# RH016_1.net
KiCad netlist of a schematic drawn in EAGLE
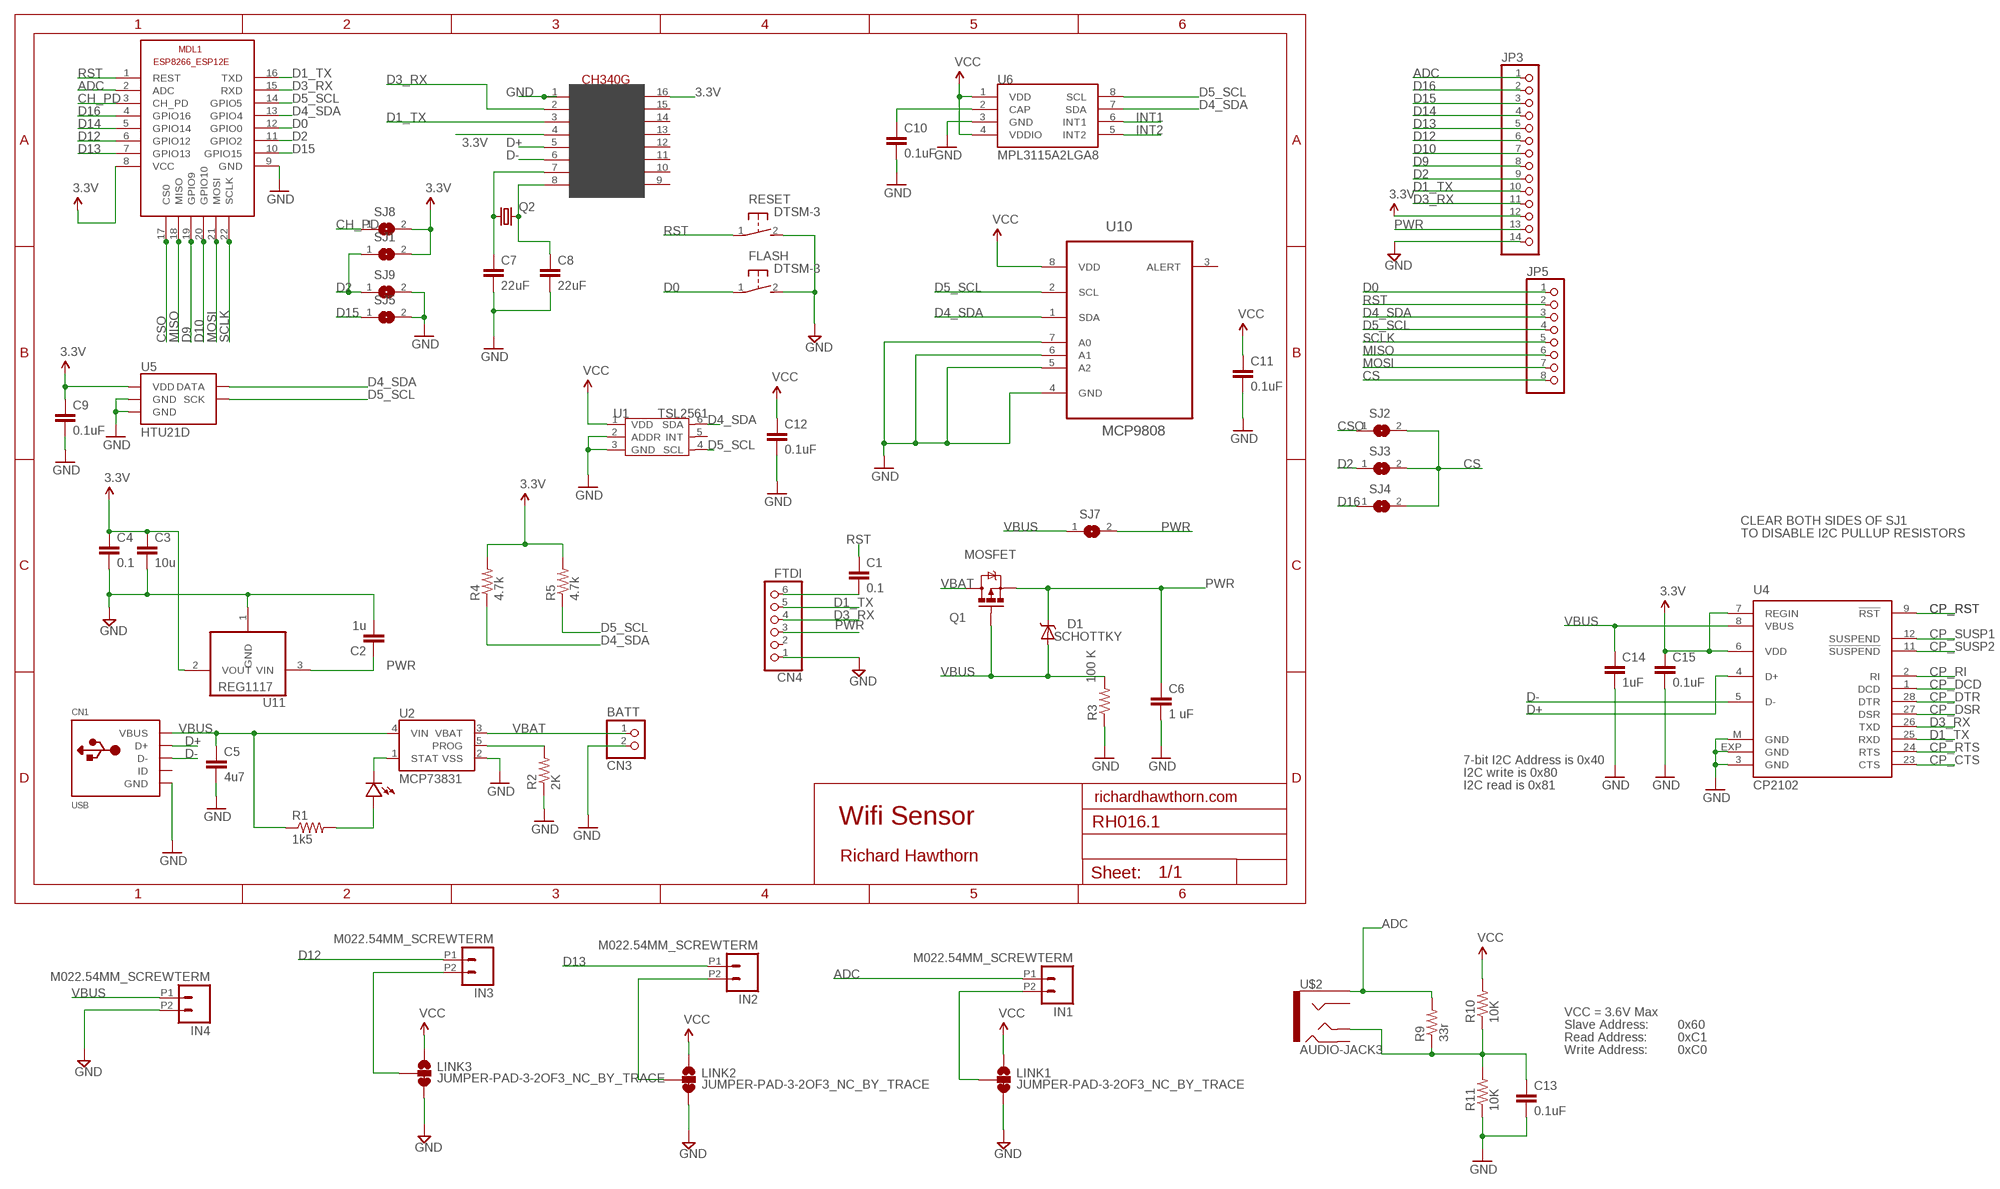
[diagram p0: schematic, sheet 1]

(export (version "E")
  (design (tool "Eeschema 10.0.6"))
  (components
    (comp (ref "C1")
      (value "0.1")
      (footprint "eagle-import:0603-CAP")
      (libsource (lib "eagle-import") (part "CAP0603-CAP"))
    )
    (comp (ref "C2")
      (value "1u")
      (footprint "eagle-import:0603-CAP")
      (libsource (lib "eagle-import") (part "CAP0603-CAP"))
    )
    (comp (ref "C3")
      (value "10u")
      (footprint "eagle-import:0805-CAP")
      (libsource (lib "eagle-import") (part "CAP0805-CAP"))
    )
    (comp (ref "C4")
      (value "0.1")
      (footprint "eagle-import:0603-CAP")
      (libsource (lib "eagle-import") (part "CAP0603-CAP"))
    )
    (comp (ref "C5")
      (value "4u7")
      (footprint "eagle-import:0603-CAP")
      (libsource (lib "eagle-import") (part "SparkFun_CAP0603-CAP"))
    )
    (comp (ref "C6")
      (value "1 uF")
      (footprint "eagle-import:0805")
      (libsource (lib "eagle-import") (part "SparkFun-Capacitors_CAP0805"))
    )
    (comp (ref "C7")
      (value "22uF")
      (footprint "eagle-import:0805")
      (libsource (lib "eagle-import") (part "SparkFun_CAP0805"))
    )
    (comp (ref "C8")
      (value "22uF")
      (footprint "eagle-import:0805")
      (libsource (lib "eagle-import") (part "SparkFun_CAP0805"))
    )
    (comp (ref "C9")
      (value "0.1uF")
      (footprint "eagle-import:0805")
      (libsource (lib "eagle-import") (part "SparkFun_CAP0805"))
    )
    (comp (ref "C10")
      (value "0.1uF")
      (footprint "eagle-import:0805")
      (libsource (lib "eagle-import") (part "SparkFun_CAP0805"))
    )
    (comp (ref "C11")
      (value "0.1uF")
      (footprint "eagle-import:0603-CAP")
      (libsource (lib "eagle-import") (part "SparkFun_CAP0603-CAP"))
    )
    (comp (ref "C12")
      (value "0.1uF")
      (footprint "eagle-import:0603-CAP")
      (libsource (lib "eagle-import") (part "SparkFun_CAP0603-CAP"))
    )
    (comp (ref "C13")
      (value "0.1uF")
      (footprint "eagle-import:0603-CAP")
      (libsource (lib "eagle-import") (part "SparkFun_CAP0603-CAP"))
    )
    (comp (ref "C14")
      (value "1uF")
      (footprint "eagle-import:0603-CAP")
      (libsource (lib "eagle-import") (part "SparkFun_CAP0603-CAP"))
    )
    (comp (ref "C15")
      (value "0.1uF")
      (footprint "eagle-import:0603-CAP")
      (libsource (lib "eagle-import") (part "SparkFun_CAP0603-CAP"))
    )
    (comp (ref "CN1")
      (value "USB")
      (footprint "eagle-import:USB-MINIB")
      (libsource (lib "eagle-import") (part "USBMINIB"))
    )
    (comp (ref "CN3")
      (value "BATT")
      (footprint "eagle-import:JST-PH-2-SMT-RA")
      (libsource (lib "eagle-import") (part "JST_2PIN-SMT-RA"))
    )
    (comp (ref "CN4")
      (value "FTDI")
      (footprint "eagle-import:1X06")
      (libsource (lib "eagle-import") (part "PINHD-1X6"))
    )
    (comp (ref "D1")
      (value "SCHOTTKY")
      (footprint "eagle-import:SMA-DIODE")
      (libsource (lib "eagle-import") (part "DIODE-SCHOTTKY_"))
    )
    (comp (ref "FLASH")
      (value "DTSM-3")
      (footprint "eagle-import:DTSM-3")
      (libsource (lib "eagle-import") (part "DTSM-3"))
    )
    (comp (ref "IN1")
      (value "M022.54MM_SCREWTERM")
      (footprint "eagle-import:1X02_2.54_SCREWTERM")
      (libsource (lib "eagle-import") (part "M022.54MM_SCREWTERM"))
    )
    (comp (ref "IN2")
      (value "M022.54MM_SCREWTERM")
      (footprint "eagle-import:1X02_2.54_SCREWTERM")
      (libsource (lib "eagle-import") (part "M022.54MM_SCREWTERM"))
    )
    (comp (ref "IN3")
      (value "M022.54MM_SCREWTERM")
      (footprint "eagle-import:1X02_2.54_SCREWTERM")
      (libsource (lib "eagle-import") (part "M022.54MM_SCREWTERM"))
    )
    (comp (ref "IN4")
      (value "M022.54MM_SCREWTERM")
      (footprint "eagle-import:1X02_2.54_SCREWTERM")
      (libsource (lib "eagle-import") (part "M022.54MM_SCREWTERM"))
    )
    (comp (ref "JP3")
      (value "PINHD-1X14")
      (footprint "eagle-import:1X14")
      (libsource (lib "eagle-import") (part "PINHD-1X14"))
    )
    (comp (ref "JP5")
      (value "PINHD-1X8")
      (footprint "eagle-import:1X08")
      (libsource (lib "eagle-import") (part "PINHD-1X8"))
    )
    (comp (ref "LED1")
      (value "LED0603")
      (footprint "eagle-import:0603-LED")
      (libsource (lib "eagle-import") (part "LED0603"))
    )
    (comp (ref "LINK1")
      (value "JUMPER-PAD-3-2OF3_NC_BY_TRACE")
      (footprint "eagle-import:PAD-JUMPER-3-2OF3_NC_BY_TRACE_YES_SILK_FULL_BOX")
      (libsource (lib "eagle-import") (part "JUMPER-PAD-3-2OF3_NC_BY_TRACE"))
    )
    (comp (ref "LINK2")
      (value "JUMPER-PAD-3-2OF3_NC_BY_TRACE")
      (footprint "eagle-import:PAD-JUMPER-3-2OF3_NC_BY_TRACE_YES_SILK_FULL_BOX")
      (libsource (lib "eagle-import") (part "JUMPER-PAD-3-2OF3_NC_BY_TRACE"))
    )
    (comp (ref "LINK3")
      (value "JUMPER-PAD-3-2OF3_NC_BY_TRACE")
      (footprint "eagle-import:PAD-JUMPER-3-2OF3_NC_BY_TRACE_YES_SILK_FULL_BOX")
      (libsource (lib "eagle-import") (part "JUMPER-PAD-3-2OF3_NC_BY_TRACE"))
    )
    (comp (ref "MDL1")
      (value "ESP8266-12EESP8266-ESP12E")
      (footprint "eagle-import:ESP8266-ESP12E")
      (libsource (lib "eagle-import") (part "ESP8266-12EESP8266-ESP12E"))
    )
    (comp (ref "Q1")
      (value "MOSFET")
      (footprint "eagle-import:SOT23-3")
      (libsource (lib "eagle-import") (part "MOSFET-PCHANNELSMD"))
    )
    (comp (ref "Q2")
      (value "CRYSTALSM49")
      (footprint "eagle-import:SM49")
      (libsource (lib "eagle-import") (part "CRYSTALSM49"))
    )
    (comp (ref "R1")
      (value "1k5")
      (footprint "eagle-import:0603-RES")
      (libsource (lib "eagle-import") (part "RESISTOR0603-RES"))
    )
    (comp (ref "R2")
      (value "2K")
      (footprint "eagle-import:0603-RES")
      (libsource (lib "eagle-import") (part "RESISTOR0603-RES"))
    )
    (comp (ref "R3")
      (value "100 K")
      (footprint "eagle-import:0805")
      (libsource (lib "eagle-import") (part "SparkFun-Resistors_RESISTOR0805-RES"))
    )
    (comp (ref "R4")
      (value "4.7k")
      (footprint "eagle-import:0805")
      (libsource (lib "eagle-import") (part "SparkFun_RESISTOR0805-RES"))
    )
    (comp (ref "R5")
      (value "4.7k")
      (footprint "eagle-import:0805")
      (libsource (lib "eagle-import") (part "SparkFun_RESISTOR0805-RES"))
    )
    (comp (ref "R9")
      (value "33r")
      (footprint "eagle-import:0603-RES")
      (libsource (lib "eagle-import") (part "SparkFun_RESISTOR0603-RES"))
    )
    (comp (ref "R10")
      (value "10K")
      (footprint "eagle-import:0603-RES")
      (libsource (lib "eagle-import") (part "SparkFun_RESISTOR0603-RES"))
    )
    (comp (ref "R11")
      (value "10K")
      (footprint "eagle-import:0603-RES")
      (libsource (lib "eagle-import") (part "SparkFun_RESISTOR0603-RES"))
    )
    (comp (ref "RESET")
      (value "DTSM-3")
      (footprint "eagle-import:DTSM-3")
      (libsource (lib "eagle-import") (part "DTSM-3"))
    )
    (comp (ref "SJ1") (value "SJ") (footprint "eagle-import:SJ") (libsource (lib "eagle-import") (part "SJ")))
    (comp (ref "SJ2") (value "SJ") (footprint "eagle-import:SJ") (libsource (lib "eagle-import") (part "SJ")))
    (comp (ref "SJ3") (value "SJ") (footprint "eagle-import:SJ") (libsource (lib "eagle-import") (part "SJ")))
    (comp (ref "SJ4") (value "SJ") (footprint "eagle-import:SJ") (libsource (lib "eagle-import") (part "SJ")))
    (comp (ref "SJ5") (value "SJ") (footprint "eagle-import:SJ") (libsource (lib "eagle-import") (part "SJ")))
    (comp (ref "SJ7") (value "SJ") (footprint "eagle-import:SJ") (libsource (lib "eagle-import") (part "SJ")))
    (comp (ref "SJ8") (value "SJ") (footprint "eagle-import:SJ") (libsource (lib "eagle-import") (part "SJ")))
    (comp (ref "SJ9") (value "SJ") (footprint "eagle-import:SJ") (libsource (lib "eagle-import") (part "SJ")))
    (comp (ref "U$2")
      (value "AUDIO-JACK3")
      (footprint "eagle-import:AUDIO-JACK-TRRS-SMD")
      (libsource (lib "eagle-import") (part "AUDIO-JACK3"))
    )
    (comp (ref "U$4")
      (value "CH340G")
      (footprint "eagle-import:SOIC16")
      (libsource (lib "eagle-import") (part "CH340G"))
    )
    (comp (ref "U1")
      (value "TSL2561")
      (footprint "eagle-import:TMB-6")
      (libsource (lib "eagle-import") (part "TSL2561T"))
    )
    (comp (ref "U2")
      (value "MCP73831")
      (footprint "eagle-import:SOT23-5")
      (libsource (lib "eagle-import") (part "MCP73831"))
    )
    (comp (ref "U4")
      (value "CP2102")
      (footprint "eagle-import:MLP28")
      (libsource (lib "eagle-import") (part "CP210X_USB_UART"))
    )
    (comp (ref "U5")
      (value "HTU21D")
      (footprint "eagle-import:HTU21D")
      (libsource (lib "eagle-import") (part "HTU21DSMD"))
    )
    (comp (ref "U6")
      (value "MPL3115A2LGA8")
      (footprint "eagle-import:LGA8")
      (libsource (lib "eagle-import") (part "MPL3115A2LGA8"))
    )
    (comp (ref "U10")
      (value "MCP9808")
      (footprint "eagle-import:SOP65P490X110-8N")
      (fields (field (name "MPN") "MCP9808-E/MS"))
      (libsource (lib "eagle-import") (part "MCP9808-E/MS"))
    )
    (comp (ref "U11")
      (value "REG1117")
      (footprint "eagle-import:SOT223")
      (libsource (lib "eagle-import") (part "REG1117"))
    )
  )
  (nets
    (net (code "1") (name "/ADC") (class "Default")
      (node (ref "IN1") (pin "P1") (pinfunction "1_P1") (pintype "passive"))
      (node (ref "JP3") (pin "1") (pinfunction "1_1") (pintype "passive"))
      (node (ref "MDL1") (pin "2") (pinfunction "ADC_2") (pintype "bidirectional"))
      (node (ref "R9") (pin "2") (pinfunction "2_2") (pintype "passive"))
      (node (ref "U$2") (pin "EARTH") (pinfunction "EARTH_EARTH") (pintype "bidirectional"))
    )
    (net (code "2") (name "/CH_PD") (class "Default")
      (node (ref "MDL1") (pin "3") (pinfunction "CH_PD_3") (pintype "bidirectional"))
      (node (ref "SJ8") (pin "1") (pinfunction "1_1") (pintype "passive"))
    )
    (net (code "3") (name "/CP_CTS") (class "Default")
      (node (ref "U4") (pin "23") (pinfunction "CTS_23") (pintype "input"))
    )
    (net (code "4") (name "/CP_DCD") (class "Default")
      (node (ref "U4") (pin "1") (pinfunction "DCD_1") (pintype "input"))
    )
    (net (code "5") (name "/CP_DSR") (class "Default")
      (node (ref "U4") (pin "27") (pinfunction "DSR_27") (pintype "input"))
    )
    (net (code "6") (name "/CP_DTR") (class "Default")
      (node (ref "U4") (pin "28") (pinfunction "DTR_28") (pintype "output"))
    )
    (net (code "7") (name "/CP_RI") (class "Default")
      (node (ref "U4") (pin "2") (pinfunction "RI_2") (pintype "input"))
    )
    (net (code "8") (name "/CP_RST") (class "Default")
      (node (ref "U4") (pin "9") (pinfunction "~{RST}_9") (pintype "bidirectional"))
    )
    (net (code "9") (name "/CP_RTS") (class "Default")
      (node (ref "U4") (pin "24") (pinfunction "RTS_24") (pintype "output"))
    )
    (net (code "10") (name "/CP_SUSP1") (class "Default")
      (node (ref "U4") (pin "12") (pinfunction "SUSPEND_12") (pintype "output"))
    )
    (net (code "11") (name "/CP_SUSP2") (class "Default")
      (node (ref "U4") (pin "11") (pinfunction "~{SUSPEND}_11") (pintype "output"))
    )
    (net (code "12") (name "/CS") (class "Default")
      (node (ref "JP5") (pin "8") (pinfunction "8_8") (pintype "passive"))
      (node (ref "SJ2") (pin "2") (pinfunction "2_2") (pintype "passive"))
      (node (ref "SJ3") (pin "2") (pinfunction "2_2") (pintype "passive"))
      (node (ref "SJ4") (pin "2") (pinfunction "2_2") (pintype "passive"))
    )
    (net (code "13") (name "/CSO") (class "Default")
      (node (ref "MDL1") (pin "17") (pinfunction "CS0_17") (pintype "bidirectional"))
      (node (ref "SJ2") (pin "1") (pinfunction "1_1") (pintype "passive"))
    )
    (net (code "14") (name "/D+") (class "Default")
      (node (ref "CN1") (pin "D+") (pinfunction "D+_D+") (pintype "bidirectional"))
      (node (ref "U$4") (pin "5") (pinfunction "D+_5") (pintype "bidirectional"))
      (node (ref "U4") (pin "4") (pinfunction "D+_4") (pintype "bidirectional"))
    )
    (net (code "15") (name "/D-") (class "Default")
      (node (ref "CN1") (pin "D-") (pinfunction "D-_D-") (pintype "bidirectional"))
      (node (ref "U$4") (pin "6") (pinfunction "D-_6") (pintype "bidirectional"))
      (node (ref "U4") (pin "5") (pinfunction "D-_5") (pintype "bidirectional"))
    )
    (net (code "16") (name "/D0") (class "Default")
      (node (ref "FLASH") (pin "1") (pinfunction "1_1") (pintype "passive"))
      (node (ref "JP5") (pin "1") (pinfunction "1_1") (pintype "passive"))
      (node (ref "MDL1") (pin "12") (pinfunction "GPIO0_12") (pintype "bidirectional"))
    )
    (net (code "17") (name "/D1_TX") (class "Default")
      (node (ref "CN4") (pin "5") (pinfunction "5_5") (pintype "passive"))
      (node (ref "JP3") (pin "10") (pinfunction "10_10") (pintype "passive"))
      (node (ref "MDL1") (pin "16") (pinfunction "TXD_16") (pintype "bidirectional"))
      (node (ref "U$4") (pin "3") (pinfunction "RX_3") (pintype "bidirectional"))
      (node (ref "U4") (pin "25") (pinfunction "RXD_25") (pintype "input"))
    )
    (net (code "18") (name "/D2") (class "Default")
      (node (ref "JP3") (pin "9") (pinfunction "9_9") (pintype "passive"))
      (node (ref "MDL1") (pin "11") (pinfunction "GPIO2_11") (pintype "bidirectional"))
      (node (ref "SJ1") (pin "1") (pinfunction "1_1") (pintype "passive"))
      (node (ref "SJ3") (pin "1") (pinfunction "1_1") (pintype "passive"))
      (node (ref "SJ9") (pin "1") (pinfunction "1_1") (pintype "passive"))
    )
    (net (code "19") (name "/D3_RX") (class "Default")
      (node (ref "CN4") (pin "4") (pinfunction "4_4") (pintype "passive"))
      (node (ref "JP3") (pin "11") (pinfunction "11_11") (pintype "passive"))
      (node (ref "MDL1") (pin "15") (pinfunction "RXD_15") (pintype "bidirectional"))
      (node (ref "U$4") (pin "2") (pinfunction "TX_2") (pintype "bidirectional"))
      (node (ref "U4") (pin "26") (pinfunction "TXD_26") (pintype "output"))
    )
    (net (code "20") (name "/D4_SDA") (class "Default")
      (node (ref "JP5") (pin "3") (pinfunction "3_3") (pintype "passive"))
      (node (ref "MDL1") (pin "13") (pinfunction "GPIO4_13") (pintype "bidirectional"))
      (node (ref "R4") (pin "1") (pinfunction "1_1") (pintype "passive"))
      (node (ref "U1") (pin "6") (pinfunction "SDA_6") (pintype "bidirectional"))
      (node (ref "U10") (pin "1") (pinfunction "SDA_1") (pintype "bidirectional"))
      (node (ref "U5") (pin "DATA") (pinfunction "DATA_DATA") (pintype "bidirectional"))
      (node (ref "U6") (pin "7") (pinfunction "SDA_7") (pintype "bidirectional"))
    )
    (net (code "21") (name "/D5_SCL") (class "Default")
      (node (ref "JP5") (pin "4") (pinfunction "4_4") (pintype "passive"))
      (node (ref "MDL1") (pin "14") (pinfunction "GPIO5_14") (pintype "bidirectional"))
      (node (ref "R5") (pin "1") (pinfunction "1_1") (pintype "passive"))
      (node (ref "U1") (pin "4") (pinfunction "SCL_4") (pintype "input"))
      (node (ref "U10") (pin "2") (pinfunction "SCL_2") (pintype "input"))
      (node (ref "U5") (pin "SCK") (pinfunction "SCK_SCK") (pintype "input"))
      (node (ref "U6") (pin "8") (pinfunction "SCL_8") (pintype "bidirectional"))
    )
    (net (code "22") (name "/D9") (class "Default")
      (node (ref "JP3") (pin "8") (pinfunction "8_8") (pintype "passive"))
      (node (ref "MDL1") (pin "19") (pinfunction "GPIO9_19") (pintype "bidirectional"))
    )
    (net (code "23") (name "/D10") (class "Default")
      (node (ref "JP3") (pin "7") (pinfunction "7_7") (pintype "passive"))
      (node (ref "MDL1") (pin "20") (pinfunction "GPIO10_20") (pintype "bidirectional"))
    )
    (net (code "24") (name "/D12") (class "Default")
      (node (ref "IN3") (pin "P1") (pinfunction "1_P1") (pintype "passive"))
      (node (ref "JP3") (pin "6") (pinfunction "6_6") (pintype "passive"))
      (node (ref "MDL1") (pin "6") (pinfunction "GPIO12_6") (pintype "bidirectional"))
    )
    (net (code "25") (name "/D13") (class "Default")
      (node (ref "IN2") (pin "P1") (pinfunction "1_P1") (pintype "passive"))
      (node (ref "JP3") (pin "5") (pinfunction "5_5") (pintype "passive"))
      (node (ref "MDL1") (pin "7") (pinfunction "GPIO13_7") (pintype "bidirectional"))
    )
    (net (code "26") (name "/D14") (class "Default")
      (node (ref "JP3") (pin "4") (pinfunction "4_4") (pintype "passive"))
      (node (ref "MDL1") (pin "5") (pinfunction "GPIO14_5") (pintype "bidirectional"))
    )
    (net (code "27") (name "/D15") (class "Default")
      (node (ref "JP3") (pin "3") (pinfunction "3_3") (pintype "passive"))
      (node (ref "MDL1") (pin "10") (pinfunction "GPIO15_10") (pintype "bidirectional"))
      (node (ref "SJ5") (pin "1") (pinfunction "1_1") (pintype "passive"))
    )
    (net (code "28") (name "/D16") (class "Default")
      (node (ref "JP3") (pin "2") (pinfunction "2_2") (pintype "passive"))
      (node (ref "MDL1") (pin "4") (pinfunction "GPIO16_4") (pintype "bidirectional"))
      (node (ref "SJ4") (pin "1") (pinfunction "1_1") (pintype "passive"))
    )
    (net (code "29") (name "/INT1") (class "Default")
      (node (ref "U6") (pin "6") (pinfunction "INT1_6") (pintype "bidirectional"))
    )
    (net (code "30") (name "/INT2") (class "Default")
      (node (ref "U6") (pin "5") (pinfunction "INT2_5") (pintype "bidirectional"))
    )
    (net (code "31") (name "/MISO") (class "Default")
      (node (ref "JP5") (pin "6") (pinfunction "6_6") (pintype "passive"))
      (node (ref "MDL1") (pin "18") (pinfunction "MISO_18") (pintype "bidirectional"))
    )
    (net (code "32") (name "/MOSI") (class "Default")
      (node (ref "JP5") (pin "7") (pinfunction "7_7") (pintype "passive"))
      (node (ref "MDL1") (pin "21") (pinfunction "MOSI_21") (pintype "bidirectional"))
    )
    (net (code "33") (name "/PWR") (class "Default")
      (node (ref "C2") (pin "1") (pinfunction "1_1") (pintype "passive"))
      (node (ref "C6") (pin "1") (pinfunction "1_1") (pintype "passive"))
      (node (ref "CN4") (pin "3") (pinfunction "3_3") (pintype "passive"))
      (node (ref "D1") (pin "C") (pinfunction "C_C") (pintype "passive"))
      (node (ref "JP3") (pin "13") (pinfunction "13_13") (pintype "passive"))
      (node (ref "Q1") (pin "2") (pinfunction "S_2") (pintype "passive"))
      (node (ref "SJ7") (pin "2") (pinfunction "2_2") (pintype "passive"))
      (node (ref "U11") (pin "3") (pinfunction "VIN_3") (pintype "input"))
    )
    (net (code "34") (name "/RST") (class "Default")
      (node (ref "C1") (pin "1") (pinfunction "1_1") (pintype "passive"))
      (node (ref "JP5") (pin "2") (pinfunction "2_2") (pintype "passive"))
      (node (ref "MDL1") (pin "1") (pinfunction "REST_1") (pintype "bidirectional"))
      (node (ref "RESET") (pin "1") (pinfunction "1_1") (pintype "passive"))
    )
    (net (code "35") (name "/SCLK") (class "Default")
      (node (ref "JP5") (pin "5") (pinfunction "5_5") (pintype "passive"))
      (node (ref "MDL1") (pin "22") (pinfunction "SCLK_22") (pintype "bidirectional"))
    )
    (net (code "36") (name "/VBAT") (class "Default")
      (node (ref "CN3") (pin "1") (pinfunction "2_1") (pintype "passive"))
      (node (ref "Q1") (pin "3") (pinfunction "D_3") (pintype "passive"))
      (node (ref "U2") (pin "3") (pinfunction "VBAT_3") (pintype "power_in"))
    )
    (net (code "37") (name "/VBUS") (class "Default")
      (node (ref "C14") (pin "1") (pinfunction "1_1") (pintype "passive"))
      (node (ref "C5") (pin "1") (pinfunction "1_1") (pintype "passive"))
      (node (ref "CN1") (pin "VBUS") (pinfunction "VBUS_VBUS") (pintype "power_in"))
      (node (ref "D1") (pin "A") (pinfunction "A_A") (pintype "passive"))
      (node (ref "IN4") (pin "P1") (pinfunction "1_P1") (pintype "passive"))
      (node (ref "Q1") (pin "1") (pinfunction "G_1") (pintype "passive"))
      (node (ref "R1") (pin "1") (pinfunction "1_1") (pintype "passive"))
      (node (ref "R3") (pin "2") (pinfunction "2_2") (pintype "passive"))
      (node (ref "SJ7") (pin "1") (pinfunction "1_1") (pintype "passive"))
      (node (ref "U2") (pin "4") (pinfunction "VIN_4") (pintype "power_in"))
      (node (ref "U4") (pin "8") (pinfunction "VBUS_8") (pintype "input"))
    )
    (net (code "38") (name "3.3V") (class "Default")
      (node (ref "C11") (pin "1") (pinfunction "1_1") (pintype "passive"))
      (node (ref "C12") (pin "1") (pinfunction "1_1") (pintype "passive"))
      (node (ref "C15") (pin "1") (pinfunction "1_1") (pintype "passive"))
      (node (ref "C3") (pin "1") (pinfunction "1_1") (pintype "passive"))
      (node (ref "C4") (pin "1") (pinfunction "1_1") (pintype "passive"))
      (node (ref "C9") (pin "1") (pinfunction "1_1") (pintype "passive"))
      (node (ref "JP3") (pin "12") (pinfunction "12_12") (pintype "passive"))
      (node (ref "LINK1") (pin "1") (pinfunction "1_1") (pintype "passive"))
      (node (ref "LINK2") (pin "1") (pinfunction "1_1") (pintype "passive"))
      (node (ref "LINK3") (pin "1") (pinfunction "1_1") (pintype "passive"))
      (node (ref "MDL1") (pin "8") (pinfunction "VCC_8") (pintype "bidirectional"))
      (node (ref "R10") (pin "2") (pinfunction "2_2") (pintype "passive"))
      (node (ref "R4") (pin "2") (pinfunction "2_2") (pintype "passive"))
      (node (ref "R5") (pin "2") (pinfunction "2_2") (pintype "passive"))
      (node (ref "SJ1") (pin "2") (pinfunction "2_2") (pintype "passive"))
      (node (ref "SJ8") (pin "2") (pinfunction "2_2") (pintype "passive"))
      (node (ref "U$4") (pin "16") (pinfunction "VCC_16") (pintype "bidirectional"))
      (node (ref "U$4") (pin "4") (pinfunction "V3_4") (pintype "bidirectional"))
      (node (ref "U1") (pin "1") (pinfunction "VDD_1") (pintype "power_in"))
      (node (ref "U10") (pin "8") (pinfunction "VDD_8") (pintype "power_in"))
      (node (ref "U11") (pin "2") (pinfunction "VOUT_2") (pintype "output"))
      (node (ref "U4") (pin "6") (pinfunction "VDD_6") (pintype "power_in"))
      (node (ref "U4") (pin "7") (pinfunction "REGIN_7") (pintype "passive"))
      (node (ref "U5") (pin "VDD") (pinfunction "VDD_VDD") (pintype "power_in"))
      (node (ref "U6") (pin "1") (pinfunction "VDD_1") (pintype "bidirectional"))
      (node (ref "U6") (pin "4") (pinfunction "VDDIO_4") (pintype "bidirectional"))
    )
    (net (code "39") (name "GND") (class "Default")
      (node (ref "C10") (pin "2") (pinfunction "2_2") (pintype "passive"))
      (node (ref "C11") (pin "2") (pinfunction "2_2") (pintype "passive"))
      (node (ref "C12") (pin "2") (pinfunction "2_2") (pintype "passive"))
      (node (ref "C13") (pin "2") (pinfunction "2_2") (pintype "passive"))
      (node (ref "C14") (pin "2") (pinfunction "2_2") (pintype "passive"))
      (node (ref "C15") (pin "2") (pinfunction "2_2") (pintype "passive"))
      (node (ref "C2") (pin "2") (pinfunction "2_2") (pintype "passive"))
      (node (ref "C3") (pin "2") (pinfunction "2_2") (pintype "passive"))
      (node (ref "C4") (pin "2") (pinfunction "2_2") (pintype "passive"))
      (node (ref "C5") (pin "2") (pinfunction "2_2") (pintype "passive"))
      (node (ref "C6") (pin "2") (pinfunction "2_2") (pintype "passive"))
      (node (ref "C7") (pin "2") (pinfunction "2_2") (pintype "passive"))
      (node (ref "C8") (pin "2") (pinfunction "2_2") (pintype "passive"))
      (node (ref "C9") (pin "2") (pinfunction "2_2") (pintype "passive"))
      (node (ref "CN1") (pin "GND") (pinfunction "GND_GND") (pintype "power_in"))
      (node (ref "CN3") (pin "2") (pinfunction "1_2") (pintype "passive"))
      (node (ref "CN4") (pin "1") (pinfunction "1_1") (pintype "passive"))
      (node (ref "FLASH") (pin "2") (pinfunction "2_2") (pintype "passive"))
      (node (ref "IN4") (pin "P2") (pinfunction "2_P2") (pintype "passive"))
      (node (ref "JP3") (pin "14") (pinfunction "14_14") (pintype "passive"))
      (node (ref "LINK1") (pin "3") (pinfunction "3_3") (pintype "passive"))
      (node (ref "LINK2") (pin "3") (pinfunction "3_3") (pintype "passive"))
      (node (ref "LINK3") (pin "3") (pinfunction "3_3") (pintype "passive"))
      (node (ref "MDL1") (pin "9") (pinfunction "GND_9") (pintype "bidirectional"))
      (node (ref "R11") (pin "1") (pinfunction "1_1") (pintype "passive"))
      (node (ref "R2") (pin "1") (pinfunction "1_1") (pintype "passive"))
      (node (ref "R3") (pin "1") (pinfunction "1_1") (pintype "passive"))
      (node (ref "RESET") (pin "2") (pinfunction "2_2") (pintype "passive"))
      (node (ref "SJ5") (pin "2") (pinfunction "2_2") (pintype "passive"))
      (node (ref "SJ9") (pin "2") (pinfunction "2_2") (pintype "passive"))
      (node (ref "U$4") (pin "1") (pinfunction "GND_1") (pintype "bidirectional"))
      (node (ref "U1") (pin "2") (pinfunction "ADDR_2") (pintype "input"))
      (node (ref "U1") (pin "3") (pinfunction "GND_3") (pintype "power_in"))
      (node (ref "U10") (pin "4") (pinfunction "GND_4") (pintype "passive"))
      (node (ref "U10") (pin "5") (pinfunction "A2_5") (pintype "input"))
      (node (ref "U10") (pin "6") (pinfunction "A1_6") (pintype "input"))
      (node (ref "U10") (pin "7") (pinfunction "A0_7") (pintype "input"))
      (node (ref "U11") (pin "1") (pinfunction "GND_1") (pintype "power_in"))
      (node (ref "U2") (pin "2") (pinfunction "VSS_2") (pintype "power_in"))
      (node (ref "U4") (pin "3") (pinfunction "GND_3") (pintype "power_in"))
      (node (ref "U4") (pin "EXP") (pinfunction "GND_EXP") (pintype "power_in"))
      (node (ref "U4") (pin "M") (pinfunction "GND_M") (pintype "power_in"))
      (node (ref "U5") (pin "7") (pinfunction "GND_7") (pintype "power_in"))
      (node (ref "U5") (pin "GND") (pinfunction "GND_GND") (pintype "power_in"))
      (node (ref "U6") (pin "3") (pinfunction "GND_3") (pintype "bidirectional"))
    )
    (net (code "40") (name "Net-(C1-Pad2)") (class "Default")
      (node (ref "C1") (pin "2") (pinfunction "2_2") (pintype "passive"))
      (node (ref "CN4") (pin "6") (pinfunction "6_6") (pintype "passive"))
    )
    (net (code "41") (name "Net-(C13-Pad1)") (class "Default")
      (node (ref "C13") (pin "1") (pinfunction "1_1") (pintype "passive"))
      (node (ref "R10") (pin "1") (pinfunction "1_1") (pintype "passive"))
      (node (ref "R11") (pin "2") (pinfunction "2_2") (pintype "passive"))
      (node (ref "R9") (pin "1") (pinfunction "1_1") (pintype "passive"))
      (node (ref "U$2") (pin "TIP") (pinfunction "TIP_TIP") (pintype "bidirectional"))
    )
    (net (code "42") (name "Net-(IN1-2)") (class "Default")
      (node (ref "IN1") (pin "P2") (pinfunction "2_P2") (pintype "passive"))
      (node (ref "LINK1") (pin "2") (pinfunction "2_2") (pintype "passive"))
    )
    (net (code "43") (name "Net-(IN2-2)") (class "Default")
      (node (ref "IN2") (pin "P2") (pinfunction "2_P2") (pintype "passive"))
      (node (ref "LINK2") (pin "2") (pinfunction "2_2") (pintype "passive"))
    )
    (net (code "44") (name "Net-(IN3-2)") (class "Default")
      (node (ref "IN3") (pin "P2") (pinfunction "2_P2") (pintype "passive"))
      (node (ref "LINK3") (pin "2") (pinfunction "2_2") (pintype "passive"))
    )
    (net (code "45") (name "Net-(LED1-PadPLUS)") (class "Default")
      (node (ref "LED1") (pin "PLUS") (pinfunction "PLUS_PLUS") (pintype "passive"))
      (node (ref "R1") (pin "2") (pinfunction "2_2") (pintype "passive"))
    )
    (net (code "46") (name "Net-(U$4-XI)") (class "Default")
      (node (ref "C7") (pin "1") (pinfunction "1_1") (pintype "passive"))
      (node (ref "Q2") (pin "1") (pinfunction "1_1") (pintype "passive"))
      (node (ref "U$4") (pin "7") (pinfunction "XI_7") (pintype "bidirectional"))
    )
    (net (code "47") (name "Net-(U$4-XO)") (class "Default")
      (node (ref "C8") (pin "1") (pinfunction "1_1") (pintype "passive"))
      (node (ref "Q2") (pin "2") (pinfunction "2_2") (pintype "passive"))
      (node (ref "U$4") (pin "8") (pinfunction "XO_8") (pintype "bidirectional"))
    )
    (net (code "48") (name "Net-(U2-PROG)") (class "Default")
      (node (ref "R2") (pin "2") (pinfunction "2_2") (pintype "passive"))
      (node (ref "U2") (pin "5") (pinfunction "PROG_5") (pintype "input"))
    )
    (net (code "49") (name "Net-(U2-STAT)") (class "Default")
      (node (ref "LED1") (pin "MINUS") (pinfunction "MINUS_MINUS") (pintype "passive"))
      (node (ref "U2") (pin "1") (pinfunction "STAT_1") (pintype "output"))
    )
    (net (code "50") (name "Net-(U6-CAP)") (class "Default")
      (node (ref "C10") (pin "1") (pinfunction "1_1") (pintype "passive"))
      (node (ref "U6") (pin "2") (pinfunction "CAP_2") (pintype "bidirectional"))
    )
    (net (code "51") (name "unconnected-(CN1-PadID)") (class "Default")
      (node (ref "CN1") (pin "ID") (pinfunction "ID_ID") (pintype "bidirectional"))
    )
    (net (code "52") (name "unconnected-(CN4-Pad2)") (class "Default")
      (node (ref "CN4") (pin "2") (pinfunction "2_2") (pintype "passive"))
    )
    (net (code "53") (name "unconnected-(U$2-PadRING1)") (class "Default")
      (node (ref "U$2") (pin "RING1") (pinfunction "RING1_RING1") (pintype "bidirectional"))
    )
    (net (code "54") (name "unconnected-(U$2-PadRING2)") (class "Default")
      (node (ref "U$2") (pin "RING2") (pinfunction "RING2_RING2") (pintype "bidirectional"))
    )
    (net (code "55") (name "unconnected-(U$4-CTS-Pad9)") (class "Default")
      (node (ref "U$4") (pin "9") (pinfunction "CTS_9") (pintype "bidirectional"))
    )
    (net (code "56") (name "unconnected-(U$4-DCD-Pad12)") (class "Default")
      (node (ref "U$4") (pin "12") (pinfunction "DCD_12") (pintype "bidirectional"))
    )
    (net (code "57") (name "unconnected-(U$4-DSR-Pad10)") (class "Default")
      (node (ref "U$4") (pin "10") (pinfunction "DSR_10") (pintype "bidirectional"))
    )
    (net (code "58") (name "unconnected-(U$4-DTR-Pad13)") (class "Default")
      (node (ref "U$4") (pin "13") (pinfunction "DTR_13") (pintype "bidirectional"))
    )
    (net (code "59") (name "unconnected-(U$4-RI-Pad11)") (class "Default")
      (node (ref "U$4") (pin "11") (pinfunction "RI_11") (pintype "bidirectional"))
    )
    (net (code "60") (name "unconnected-(U$4-RS232-Pad15)") (class "Default")
      (node (ref "U$4") (pin "15") (pinfunction "RS232_15") (pintype "bidirectional"))
    )
    (net (code "61") (name "unconnected-(U$4-RTS-Pad14)") (class "Default")
      (node (ref "U$4") (pin "14") (pinfunction "RTS_14") (pintype "bidirectional"))
    )
    (net (code "62") (name "unconnected-(U1-INT-Pad5)") (class "Default")
      (node (ref "U1") (pin "5") (pinfunction "INT_5") (pintype "output"))
    )
    (net (code "63") (name "unconnected-(U10-ALERT-Pad3)") (class "Default")
      (node (ref "U10") (pin "3") (pinfunction "ALERT_3") (pintype "output"))
    )
  )
)
